# sch_expansion.net
KiCad netlist of a schematic drawn in Altium Designer
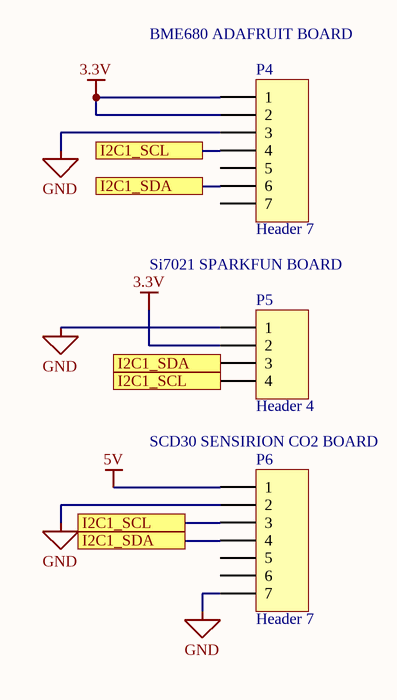
[diagram p0: sch_expansion.SchDoc]

(export (version "E")
  (design (tool "Eeschema 10.0.6"))
  (components
    (comp (ref "P4")
      (value "Header 7")
      (footprint "HDR1X7")
      (description "Header, 7-Pin")
      (fields (field (name "PUBLISHER") "Altium Limited"))
      (libsource (lib "Miscellaneous Connectors") (part "Header 7"))
    )
    (comp (ref "P5")
      (value "Header 4")
      (footprint "HDR1X4")
      (description "Header, 4-Pin")
      (fields (field (name "PUBLISHER") "Altium Limited"))
      (libsource (lib "Miscellaneous Connectors") (part "Header 4"))
    )
    (comp (ref "P6")
      (value "Header 7")
      (footprint "HDR1X7")
      (description "Header, 7-Pin")
      (fields (field (name "PUBLISHER") "Altium Limited"))
      (libsource (lib "Miscellaneous Connectors") (part "Header 7"))
    )
  )
  (nets
    (net (code "1") (name "/I2C1_SCL") (class "Default")
      (node (ref "P4") (pin "4") (pinfunction "4_4") (pintype "passive"))
      (node (ref "P5") (pin "4") (pinfunction "4_4") (pintype "passive"))
      (node (ref "P6") (pin "3") (pinfunction "3_3") (pintype "passive"))
    )
    (net (code "2") (name "/I2C1_SDA") (class "Default")
      (node (ref "P4") (pin "6") (pinfunction "6_6") (pintype "passive"))
      (node (ref "P5") (pin "3") (pinfunction "3_3") (pintype "passive"))
      (node (ref "P6") (pin "4") (pinfunction "4_4") (pintype "passive"))
    )
    (net (code "3") (name "3.3V") (class "Default")
      (node (ref "P4") (pin "1") (pinfunction "1_1") (pintype "passive"))
      (node (ref "P4") (pin "2") (pinfunction "2_2") (pintype "passive"))
      (node (ref "P5") (pin "2") (pinfunction "2_2") (pintype "passive"))
    )
    (net (code "4") (name "5V") (class "Default")
      (node (ref "P6") (pin "1") (pinfunction "1_1") (pintype "passive"))
    )
    (net (code "5") (name "GND") (class "Default")
      (node (ref "P4") (pin "3") (pinfunction "3_3") (pintype "passive"))
      (node (ref "P5") (pin "1") (pinfunction "1_1") (pintype "passive"))
      (node (ref "P6") (pin "2") (pinfunction "2_2") (pintype "passive"))
      (node (ref "P6") (pin "7") (pinfunction "7_7") (pintype "passive"))
    )
    (net (code "6") (name "unconnected-(P4-Pad5)") (class "Default")
      (node (ref "P4") (pin "5") (pinfunction "5_5") (pintype "passive"))
    )
    (net (code "7") (name "unconnected-(P4-Pad7)") (class "Default")
      (node (ref "P4") (pin "7") (pinfunction "7_7") (pintype "passive"))
    )
    (net (code "8") (name "unconnected-(P6-Pad5)") (class "Default")
      (node (ref "P6") (pin "5") (pinfunction "5_5") (pintype "passive"))
    )
    (net (code "9") (name "unconnected-(P6-Pad6)") (class "Default")
      (node (ref "P6") (pin "6") (pinfunction "6_6") (pintype "passive"))
    )
  )
)
